# ColorSense.net
KiCad netlist of a schematic drawn in EAGLE
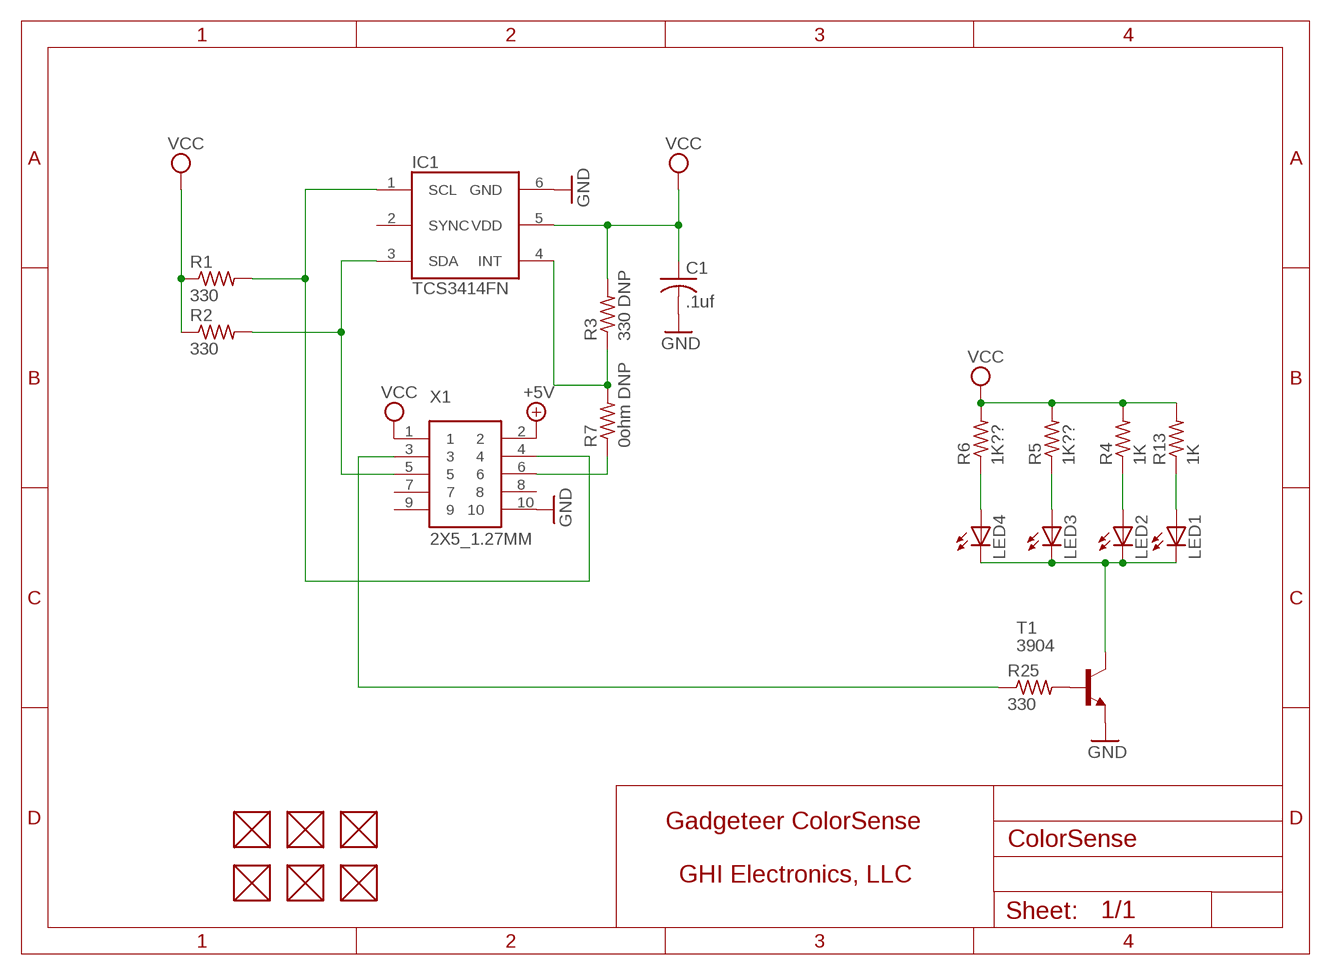
[diagram p0: schematic, sheet 1]

(export (version "E")
  (design (tool "Eeschema 10.0.6"))
  (components
    (comp (ref "C1")
      (value ".1uf")
      (footprint "eagle-import:C0603K")
      (libsource (lib "eagle-import") (part "C-USC0603K"))
    )
    (comp (ref "FUD1")
      (value "FIDUCIAL")
      (footprint "eagle-import:FIDUCIAL_40MIL")
      (libsource (lib "eagle-import") (part "FIDUCIAL"))
    )
    (comp (ref "FUD2")
      (value "FIDUCIAL")
      (footprint "eagle-import:FIDUCIAL_40MIL")
      (libsource (lib "eagle-import") (part "FIDUCIAL"))
    )
    (comp (ref "FUD3")
      (value "FIDUCIAL")
      (footprint "eagle-import:FIDUCIAL_40MIL")
      (libsource (lib "eagle-import") (part "FIDUCIAL"))
    )
    (comp (ref "FUD4")
      (value "FIDUCIAL")
      (footprint "eagle-import:FIDUCIAL_40MIL")
      (libsource (lib "eagle-import") (part "FIDUCIAL"))
    )
    (comp (ref "FUD5")
      (value "FIDUCIAL")
      (footprint "eagle-import:FIDUCIAL_40MIL")
      (libsource (lib "eagle-import") (part "FIDUCIAL"))
    )
    (comp (ref "FUD6")
      (value "FIDUCIAL")
      (footprint "eagle-import:FIDUCIAL_40MIL")
      (libsource (lib "eagle-import") (part "FIDUCIAL"))
    )
    (comp (ref "IC1")
      (value "TCS3414FN")
      (footprint "eagle-import:DFN-6")
      (libsource (lib "eagle-import") (part "TCS3414FN"))
    )
    (comp (ref "LED1")
      (value "LEDCHIPLED_0805")
      (footprint "eagle-import:CHIPLED_0805")
      (libsource (lib "eagle-import") (part "LEDCHIPLED_0805"))
    )
    (comp (ref "LED2")
      (value "LEDCHIPLED_0805")
      (footprint "eagle-import:CHIPLED_0805")
      (libsource (lib "eagle-import") (part "LEDCHIPLED_0805"))
    )
    (comp (ref "LED3")
      (value "LEDCHIPLED_0805")
      (footprint "eagle-import:CHIPLED_0805")
      (libsource (lib "eagle-import") (part "LEDCHIPLED_0805"))
    )
    (comp (ref "LED4")
      (value "LEDCHIPLED_0805")
      (footprint "eagle-import:CHIPLED_0805")
      (libsource (lib "eagle-import") (part "LEDCHIPLED_0805"))
    )
    (comp (ref "R1")
      (value "330")
      (footprint "eagle-import:R0603")
      (libsource (lib "eagle-import") (part "R-US_R0603"))
    )
    (comp (ref "R2")
      (value "330")
      (footprint "eagle-import:R0603")
      (libsource (lib "eagle-import") (part "R-US_R0603"))
    )
    (comp (ref "R3")
      (value "330 DNP")
      (footprint "eagle-import:R0603")
      (libsource (lib "eagle-import") (part "R-US_R0603"))
    )
    (comp (ref "R4")
      (value "1K")
      (footprint "eagle-import:R0603")
      (libsource (lib "eagle-import") (part "R-US_R0603"))
    )
    (comp (ref "R5")
      (value "1K??")
      (footprint "eagle-import:R0603")
      (libsource (lib "eagle-import") (part "R-US_R0603"))
    )
    (comp (ref "R6")
      (value "1K??")
      (footprint "eagle-import:R0603")
      (libsource (lib "eagle-import") (part "R-US_R0603"))
    )
    (comp (ref "R7")
      (value "0ohm DNP")
      (footprint "eagle-import:R0603")
      (libsource (lib "eagle-import") (part "R-US_R0603"))
    )
    (comp (ref "R13")
      (value "1K")
      (footprint "eagle-import:R0603")
      (libsource (lib "eagle-import") (part "R-US_R0603"))
    )
    (comp (ref "R25")
      (value "330")
      (footprint "eagle-import:R0603")
      (libsource (lib "eagle-import") (part "R-US_R0603"))
    )
    (comp (ref "T1")
      (value "3904")
      (footprint "eagle-import:SOT23-BEC")
      (libsource (lib "eagle-import") (part "-NPN-SOT23-BECBC847"))
    )
    (comp (ref "X1")
      (value "2X5_1.27MM")
      (footprint "eagle-import:2X5_1.27MM")
      (libsource (lib "eagle-import") (part "2X5_1.27MM"))
    )
  )
  (nets
    (net (code "1") (name "+5V") (class "Default")
      (node (ref "X1") (pin "2") (pinfunction "2_2") (pintype "bidirectional"))
    )
    (net (code "2") (name "GND") (class "Default")
      (node (ref "C1") (pin "2") (pinfunction "2_2") (pintype "passive"))
      (node (ref "IC1") (pin "6") (pinfunction "GND_6") (pintype "bidirectional"))
      (node (ref "T1") (pin "E") (pinfunction "E_E") (pintype "passive"))
      (node (ref "X1") (pin "10") (pinfunction "10_10") (pintype "bidirectional"))
    )
    (net (code "3") (name "Net-(IC1-INT)") (class "Default")
      (node (ref "IC1") (pin "4") (pinfunction "INT_4") (pintype "bidirectional"))
      (node (ref "R3") (pin "1") (pinfunction "1_1") (pintype "passive"))
      (node (ref "R7") (pin "2") (pinfunction "2_2") (pintype "passive"))
    )
    (net (code "4") (name "Net-(IC1-SCL)") (class "Default")
      (node (ref "IC1") (pin "1") (pinfunction "SCL_1") (pintype "bidirectional"))
      (node (ref "R1") (pin "2") (pinfunction "2_2") (pintype "passive"))
      (node (ref "X1") (pin "4") (pinfunction "4_4") (pintype "bidirectional"))
    )
    (net (code "5") (name "Net-(IC1-SDA)") (class "Default")
      (node (ref "IC1") (pin "3") (pinfunction "SDA_3") (pintype "bidirectional"))
      (node (ref "R2") (pin "2") (pinfunction "2_2") (pintype "passive"))
      (node (ref "X1") (pin "5") (pinfunction "5_5") (pintype "bidirectional"))
    )
    (net (code "6") (name "Net-(LED1-PadA)") (class "Default")
      (node (ref "LED1") (pin "A") (pinfunction "A_A") (pintype "passive"))
      (node (ref "R13") (pin "1") (pinfunction "1_1") (pintype "passive"))
    )
    (net (code "7") (name "Net-(LED1-PadC)") (class "Default")
      (node (ref "LED1") (pin "C") (pinfunction "C_C") (pintype "passive"))
      (node (ref "LED2") (pin "C") (pinfunction "C_C") (pintype "passive"))
      (node (ref "LED3") (pin "C") (pinfunction "C_C") (pintype "passive"))
      (node (ref "LED4") (pin "C") (pinfunction "C_C") (pintype "passive"))
      (node (ref "T1") (pin "C") (pinfunction "C_C") (pintype "passive"))
    )
    (net (code "8") (name "Net-(LED2-PadA)") (class "Default")
      (node (ref "LED2") (pin "A") (pinfunction "A_A") (pintype "passive"))
      (node (ref "R4") (pin "1") (pinfunction "1_1") (pintype "passive"))
    )
    (net (code "9") (name "Net-(LED3-PadA)") (class "Default")
      (node (ref "LED3") (pin "A") (pinfunction "A_A") (pintype "passive"))
      (node (ref "R5") (pin "1") (pinfunction "1_1") (pintype "passive"))
    )
    (net (code "10") (name "Net-(LED4-PadA)") (class "Default")
      (node (ref "LED4") (pin "A") (pinfunction "A_A") (pintype "passive"))
      (node (ref "R6") (pin "1") (pinfunction "1_1") (pintype "passive"))
    )
    (net (code "11") (name "Net-(R7-Pad1)") (class "Default")
      (node (ref "R7") (pin "1") (pinfunction "1_1") (pintype "passive"))
      (node (ref "X1") (pin "6") (pinfunction "6_6") (pintype "bidirectional"))
    )
    (net (code "12") (name "Net-(R25-Pad1)") (class "Default")
      (node (ref "R25") (pin "1") (pinfunction "1_1") (pintype "passive"))
      (node (ref "X1") (pin "3") (pinfunction "3_3") (pintype "bidirectional"))
    )
    (net (code "13") (name "Net-(R25-Pad2)") (class "Default")
      (node (ref "R25") (pin "2") (pinfunction "2_2") (pintype "passive"))
      (node (ref "T1") (pin "B") (pinfunction "B_B") (pintype "passive"))
    )
    (net (code "14") (name "VCC") (class "Default")
      (node (ref "C1") (pin "1") (pinfunction "1_1") (pintype "passive"))
      (node (ref "IC1") (pin "5") (pinfunction "VDD_5") (pintype "bidirectional"))
      (node (ref "R1") (pin "1") (pinfunction "1_1") (pintype "passive"))
      (node (ref "R13") (pin "2") (pinfunction "2_2") (pintype "passive"))
      (node (ref "R2") (pin "1") (pinfunction "1_1") (pintype "passive"))
      (node (ref "R3") (pin "2") (pinfunction "2_2") (pintype "passive"))
      (node (ref "R4") (pin "2") (pinfunction "2_2") (pintype "passive"))
      (node (ref "R5") (pin "2") (pinfunction "2_2") (pintype "passive"))
      (node (ref "R6") (pin "2") (pinfunction "2_2") (pintype "passive"))
      (node (ref "X1") (pin "1") (pinfunction "1_1") (pintype "bidirectional"))
    )
    (net (code "15") (name "unconnected-(FUD1-PadP$1)") (class "Default")
      (node (ref "FUD1") (pin "P$1") (pinfunction "P$1_P$1") (pintype "no_connect"))
    )
    (net (code "16") (name "unconnected-(FUD2-PadP$1)") (class "Default")
      (node (ref "FUD2") (pin "P$1") (pinfunction "P$1_P$1") (pintype "no_connect"))
    )
    (net (code "17") (name "unconnected-(FUD3-PadP$1)") (class "Default")
      (node (ref "FUD3") (pin "P$1") (pinfunction "P$1_P$1") (pintype "no_connect"))
    )
    (net (code "18") (name "unconnected-(FUD4-PadP$1)") (class "Default")
      (node (ref "FUD4") (pin "P$1") (pinfunction "P$1_P$1") (pintype "no_connect"))
    )
    (net (code "19") (name "unconnected-(FUD5-PadP$1)") (class "Default")
      (node (ref "FUD5") (pin "P$1") (pinfunction "P$1_P$1") (pintype "no_connect"))
    )
    (net (code "20") (name "unconnected-(FUD6-PadP$1)") (class "Default")
      (node (ref "FUD6") (pin "P$1") (pinfunction "P$1_P$1") (pintype "no_connect"))
    )
    (net (code "21") (name "unconnected-(IC1-SYNC-Pad2)") (class "Default")
      (node (ref "IC1") (pin "2") (pinfunction "SYNC_2") (pintype "bidirectional"))
    )
    (net (code "22") (name "unconnected-(X1-Pad7)") (class "Default")
      (node (ref "X1") (pin "7") (pinfunction "7_7") (pintype "bidirectional"))
    )
    (net (code "23") (name "unconnected-(X1-Pad8)") (class "Default")
      (node (ref "X1") (pin "8") (pinfunction "8_8") (pintype "bidirectional"))
    )
    (net (code "24") (name "unconnected-(X1-Pad9)") (class "Default")
      (node (ref "X1") (pin "9") (pinfunction "9_9") (pintype "bidirectional"))
    )
  )
)
